# PROTECTION_BUS_CAN.net
KiCad netlist of a schematic drawn in Altium Designer
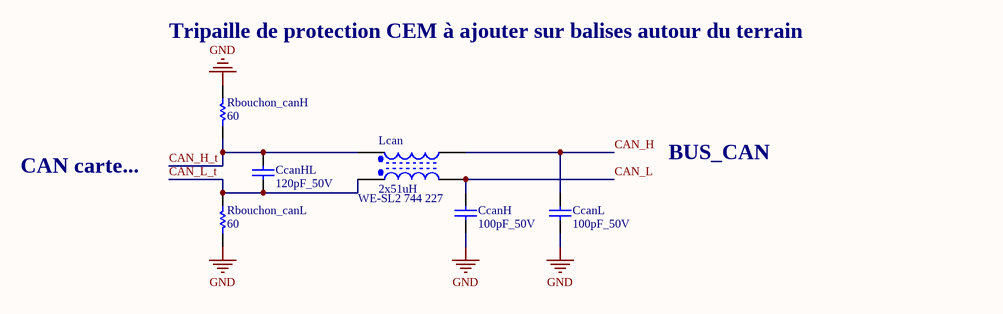
[diagram p0: PROTECTION_BUS_CAN.SchDoc]

(export (version "E")
  (design (tool "Eeschema 10.0.6"))
  (components
    (comp (ref "CcanH")
      (value "100pF_50V")
      (footprint "C0805_N")
      (description "Capacitor")
      (fields (field (name "PUBLISHER") "Altium Limited"))
      (libsource (lib "DG_Condensateur") (part "Capacitor"))
    )
    (comp (ref "CcanHL")
      (value "120pF_50V")
      (footprint "C0805_N")
      (description "Capacitor")
      (fields (field (name "PUBLISHER") "Altium Limited"))
      (libsource (lib "DG_Condensateur") (part "Capacitor"))
    )
    (comp (ref "CcanL")
      (value "100pF_50V")
      (footprint "C0805_N")
      (description "Capacitor")
      (fields (field (name "PUBLISHER") "Altium Limited"))
      (libsource (lib "DG_Condensateur") (part "Capacitor"))
    )
    (comp (ref "Lcan")
      (value "2x51uH")
      (footprint "Self de mode commun Wurth Elektronik WE-SL2")
      (description "WUERTH ELEKTRONIK - WE-SL2 744 227 - FILTRE DE LIGNE MODE COMMUN CMS 2X51uH")
      (fields
        (field (name "MANUFACTURER") "WURTH ELEKTRONIK")
        (field (name "MANUFACTURER PART NUMBER") "WE-SL2 744 227")
      )
      (libsource (lib "DG_Inductance") (part "Self de mode commun WE-744220"))
    )
    (comp (ref "Rbouchon_canH")
      (value "60")
      (footprint "R1206_N")
      (description "Resistor")
      (libsource (lib "DG_discret") (part "Resistor"))
    )
    (comp (ref "Rbouchon_canL")
      (value "60")
      (footprint "R1206_N")
      (description "Resistor")
      (libsource (lib "DG_discret") (part "Resistor"))
    )
  )
  (nets
    (net (code "1") (name "/CAN_H") (class "Default")
      (node (ref "CcanL") (pin "2") (pinfunction "2_2") (pintype "passive"))
      (node (ref "Lcan") (pin "3") (pinfunction "3_3") (pintype "passive"))
    )
    (net (code "2") (name "/CAN_H_t") (class "Default")
      (node (ref "CcanHL") (pin "2") (pinfunction "2_2") (pintype "passive"))
      (node (ref "Lcan") (pin "2") (pinfunction "2_2") (pintype "passive"))
      (node (ref "Rbouchon_canH") (pin "1") (pinfunction "1_1") (pintype "passive"))
    )
    (net (code "3") (name "/CAN_L") (class "Default")
      (node (ref "CcanH") (pin "2") (pinfunction "2_2") (pintype "passive"))
      (node (ref "Lcan") (pin "4") (pinfunction "4_4") (pintype "passive"))
    )
    (net (code "4") (name "/CAN_L_t") (class "Default")
      (node (ref "CcanHL") (pin "1") (pinfunction "1_1") (pintype "passive"))
      (node (ref "Lcan") (pin "1") (pinfunction "1_1") (pintype "passive"))
      (node (ref "Rbouchon_canL") (pin "2") (pinfunction "2_2") (pintype "passive"))
    )
    (net (code "5") (name "GND") (class "Default")
      (node (ref "CcanH") (pin "1") (pinfunction "1_1") (pintype "passive"))
      (node (ref "CcanL") (pin "1") (pinfunction "1_1") (pintype "passive"))
      (node (ref "Rbouchon_canH") (pin "2") (pinfunction "2_2") (pintype "passive"))
      (node (ref "Rbouchon_canL") (pin "1") (pinfunction "1_1") (pintype "passive"))
    )
  )
)
